# Adapter_1_1.net
KiCad netlist of a schematic drawn in EAGLE
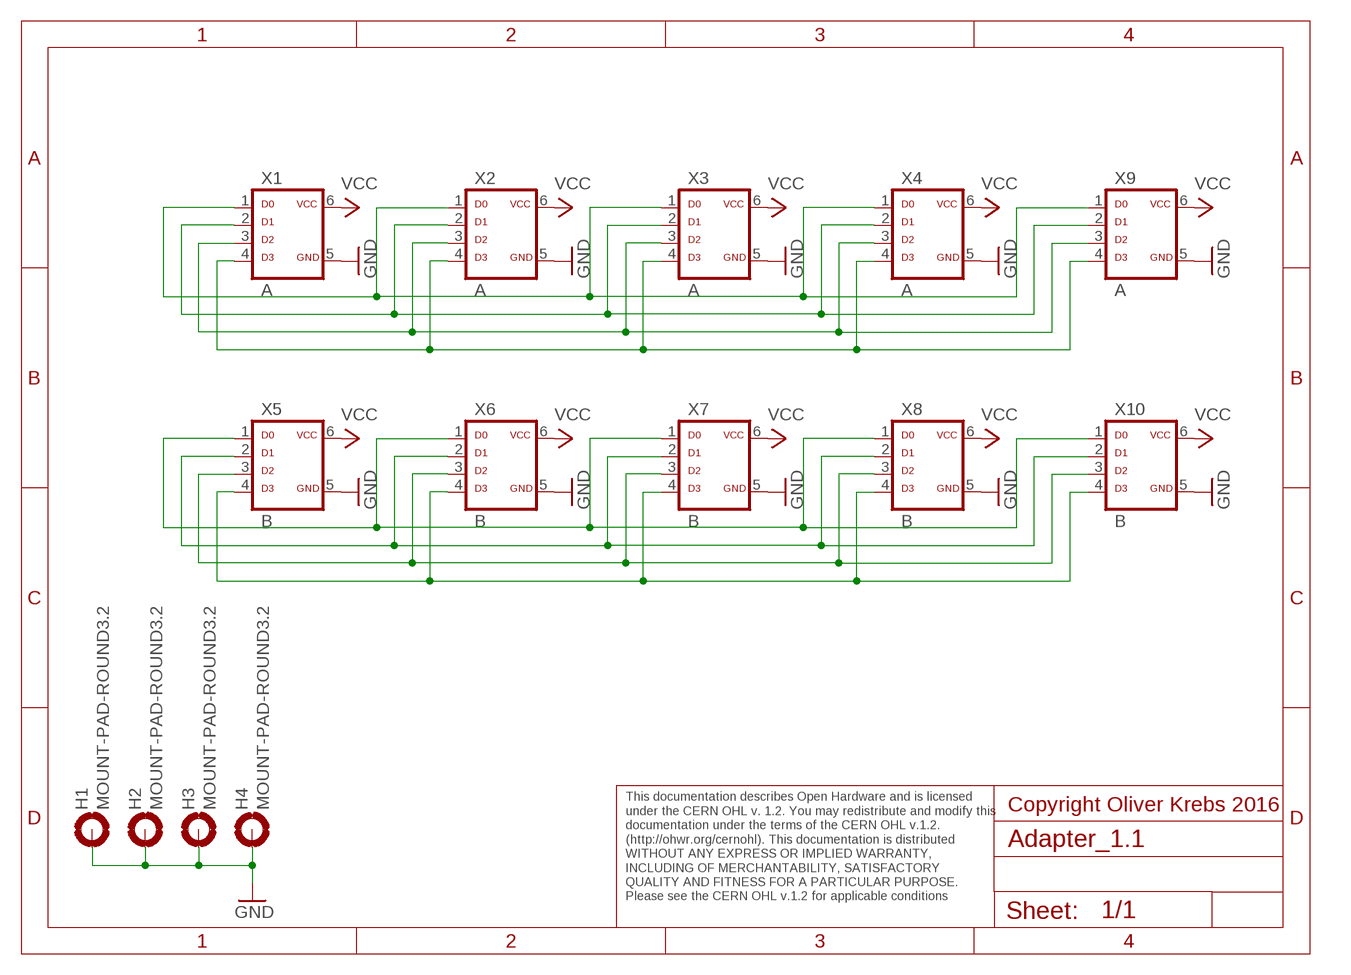
[diagram p0: schematic, sheet 1]

(export (version "E")
  (design (tool "Eeschema 10.0.6"))
  (components
    (comp (ref "H1")
      (value "MOUNT-PAD-ROUND3.2")
      (footprint "eagle-import:3,2-PAD")
      (libsource (lib "eagle-import") (part "MOUNT-PAD-ROUND3.2"))
    )
    (comp (ref "H2")
      (value "MOUNT-PAD-ROUND3.2")
      (footprint "eagle-import:3,2-PAD")
      (libsource (lib "eagle-import") (part "MOUNT-PAD-ROUND3.2"))
    )
    (comp (ref "H3")
      (value "MOUNT-PAD-ROUND3.2")
      (footprint "eagle-import:3,2-PAD")
      (libsource (lib "eagle-import") (part "MOUNT-PAD-ROUND3.2"))
    )
    (comp (ref "H4")
      (value "MOUNT-PAD-ROUND3.2")
      (footprint "eagle-import:3,2-PAD")
      (libsource (lib "eagle-import") (part "MOUNT-PAD-ROUND3.2"))
    )
    (comp (ref "X1")
      (value "A")
      (footprint "eagle-import:ML-6")
      (libsource (lib "eagle-import") (part "ML6D"))
    )
    (comp (ref "X2")
      (value "A")
      (footprint "eagle-import:ML-6")
      (libsource (lib "eagle-import") (part "ML6D"))
    )
    (comp (ref "X3")
      (value "A")
      (footprint "eagle-import:ML-6")
      (libsource (lib "eagle-import") (part "ML6D"))
    )
    (comp (ref "X4")
      (value "A")
      (footprint "eagle-import:ML-6")
      (libsource (lib "eagle-import") (part "ML6D"))
    )
    (comp (ref "X5")
      (value "B")
      (footprint "eagle-import:ML-6")
      (libsource (lib "eagle-import") (part "ML6D"))
    )
    (comp (ref "X6")
      (value "B")
      (footprint "eagle-import:ML-6")
      (libsource (lib "eagle-import") (part "ML6D"))
    )
    (comp (ref "X7")
      (value "B")
      (footprint "eagle-import:ML-6")
      (libsource (lib "eagle-import") (part "ML6D"))
    )
    (comp (ref "X8")
      (value "B")
      (footprint "eagle-import:ML-6")
      (libsource (lib "eagle-import") (part "ML6D"))
    )
    (comp (ref "X9")
      (value "A")
      (footprint "eagle-import:ML-6")
      (libsource (lib "eagle-import") (part "ML6D"))
    )
    (comp (ref "X10")
      (value "B")
      (footprint "eagle-import:ML-6")
      (libsource (lib "eagle-import") (part "ML6D"))
    )
  )
  (nets
    (net (code "1") (name "GND") (class "Default")
      (node (ref "H1") (pin "B3,2") (pinfunction "MOUNT_B3,2") (pintype "passive"))
      (node (ref "H2") (pin "B3,2") (pinfunction "MOUNT_B3,2") (pintype "passive"))
      (node (ref "H3") (pin "B3,2") (pinfunction "MOUNT_B3,2") (pintype "passive"))
      (node (ref "H4") (pin "B3,2") (pinfunction "MOUNT_B3,2") (pintype "passive"))
      (node (ref "X1") (pin "5") (pinfunction "5_5") (pintype "passive"))
      (node (ref "X10") (pin "5") (pinfunction "5_5") (pintype "passive"))
      (node (ref "X2") (pin "5") (pinfunction "5_5") (pintype "passive"))
      (node (ref "X3") (pin "5") (pinfunction "5_5") (pintype "passive"))
      (node (ref "X4") (pin "5") (pinfunction "5_5") (pintype "passive"))
      (node (ref "X5") (pin "5") (pinfunction "5_5") (pintype "passive"))
      (node (ref "X6") (pin "5") (pinfunction "5_5") (pintype "passive"))
      (node (ref "X7") (pin "5") (pinfunction "5_5") (pintype "passive"))
      (node (ref "X8") (pin "5") (pinfunction "5_5") (pintype "passive"))
      (node (ref "X9") (pin "5") (pinfunction "5_5") (pintype "passive"))
    )
    (net (code "2") (name "Net-(X1-Pad1)") (class "Default")
      (node (ref "X1") (pin "1") (pinfunction "1_1") (pintype "passive"))
      (node (ref "X2") (pin "1") (pinfunction "1_1") (pintype "passive"))
      (node (ref "X3") (pin "1") (pinfunction "1_1") (pintype "passive"))
      (node (ref "X4") (pin "1") (pinfunction "1_1") (pintype "passive"))
      (node (ref "X9") (pin "1") (pinfunction "1_1") (pintype "passive"))
    )
    (net (code "3") (name "Net-(X1-Pad2)") (class "Default")
      (node (ref "X1") (pin "2") (pinfunction "2_2") (pintype "passive"))
      (node (ref "X2") (pin "2") (pinfunction "2_2") (pintype "passive"))
      (node (ref "X3") (pin "2") (pinfunction "2_2") (pintype "passive"))
      (node (ref "X4") (pin "2") (pinfunction "2_2") (pintype "passive"))
      (node (ref "X9") (pin "2") (pinfunction "2_2") (pintype "passive"))
    )
    (net (code "4") (name "Net-(X1-Pad3)") (class "Default")
      (node (ref "X1") (pin "3") (pinfunction "3_3") (pintype "passive"))
      (node (ref "X2") (pin "3") (pinfunction "3_3") (pintype "passive"))
      (node (ref "X3") (pin "3") (pinfunction "3_3") (pintype "passive"))
      (node (ref "X4") (pin "3") (pinfunction "3_3") (pintype "passive"))
      (node (ref "X9") (pin "3") (pinfunction "3_3") (pintype "passive"))
    )
    (net (code "5") (name "Net-(X1-Pad4)") (class "Default")
      (node (ref "X1") (pin "4") (pinfunction "4_4") (pintype "passive"))
      (node (ref "X2") (pin "4") (pinfunction "4_4") (pintype "passive"))
      (node (ref "X3") (pin "4") (pinfunction "4_4") (pintype "passive"))
      (node (ref "X4") (pin "4") (pinfunction "4_4") (pintype "passive"))
      (node (ref "X9") (pin "4") (pinfunction "4_4") (pintype "passive"))
    )
    (net (code "6") (name "Net-(X10-Pad1)") (class "Default")
      (node (ref "X10") (pin "1") (pinfunction "1_1") (pintype "passive"))
      (node (ref "X5") (pin "1") (pinfunction "1_1") (pintype "passive"))
      (node (ref "X6") (pin "1") (pinfunction "1_1") (pintype "passive"))
      (node (ref "X7") (pin "1") (pinfunction "1_1") (pintype "passive"))
      (node (ref "X8") (pin "1") (pinfunction "1_1") (pintype "passive"))
    )
    (net (code "7") (name "Net-(X10-Pad2)") (class "Default")
      (node (ref "X10") (pin "2") (pinfunction "2_2") (pintype "passive"))
      (node (ref "X5") (pin "2") (pinfunction "2_2") (pintype "passive"))
      (node (ref "X6") (pin "2") (pinfunction "2_2") (pintype "passive"))
      (node (ref "X7") (pin "2") (pinfunction "2_2") (pintype "passive"))
      (node (ref "X8") (pin "2") (pinfunction "2_2") (pintype "passive"))
    )
    (net (code "8") (name "Net-(X10-Pad3)") (class "Default")
      (node (ref "X10") (pin "3") (pinfunction "3_3") (pintype "passive"))
      (node (ref "X5") (pin "3") (pinfunction "3_3") (pintype "passive"))
      (node (ref "X6") (pin "3") (pinfunction "3_3") (pintype "passive"))
      (node (ref "X7") (pin "3") (pinfunction "3_3") (pintype "passive"))
      (node (ref "X8") (pin "3") (pinfunction "3_3") (pintype "passive"))
    )
    (net (code "9") (name "Net-(X10-Pad4)") (class "Default")
      (node (ref "X10") (pin "4") (pinfunction "4_4") (pintype "passive"))
      (node (ref "X5") (pin "4") (pinfunction "4_4") (pintype "passive"))
      (node (ref "X6") (pin "4") (pinfunction "4_4") (pintype "passive"))
      (node (ref "X7") (pin "4") (pinfunction "4_4") (pintype "passive"))
      (node (ref "X8") (pin "4") (pinfunction "4_4") (pintype "passive"))
    )
    (net (code "10") (name "VCC") (class "Default")
      (node (ref "X1") (pin "6") (pinfunction "6_6") (pintype "passive"))
      (node (ref "X10") (pin "6") (pinfunction "6_6") (pintype "passive"))
      (node (ref "X2") (pin "6") (pinfunction "6_6") (pintype "passive"))
      (node (ref "X3") (pin "6") (pinfunction "6_6") (pintype "passive"))
      (node (ref "X4") (pin "6") (pinfunction "6_6") (pintype "passive"))
      (node (ref "X5") (pin "6") (pinfunction "6_6") (pintype "passive"))
      (node (ref "X6") (pin "6") (pinfunction "6_6") (pintype "passive"))
      (node (ref "X7") (pin "6") (pinfunction "6_6") (pintype "passive"))
      (node (ref "X8") (pin "6") (pinfunction "6_6") (pintype "passive"))
      (node (ref "X9") (pin "6") (pinfunction "6_6") (pintype "passive"))
    )
  )
)
